# elysium_v0_8.net
KiCad netlist of a schematic drawn in EAGLE
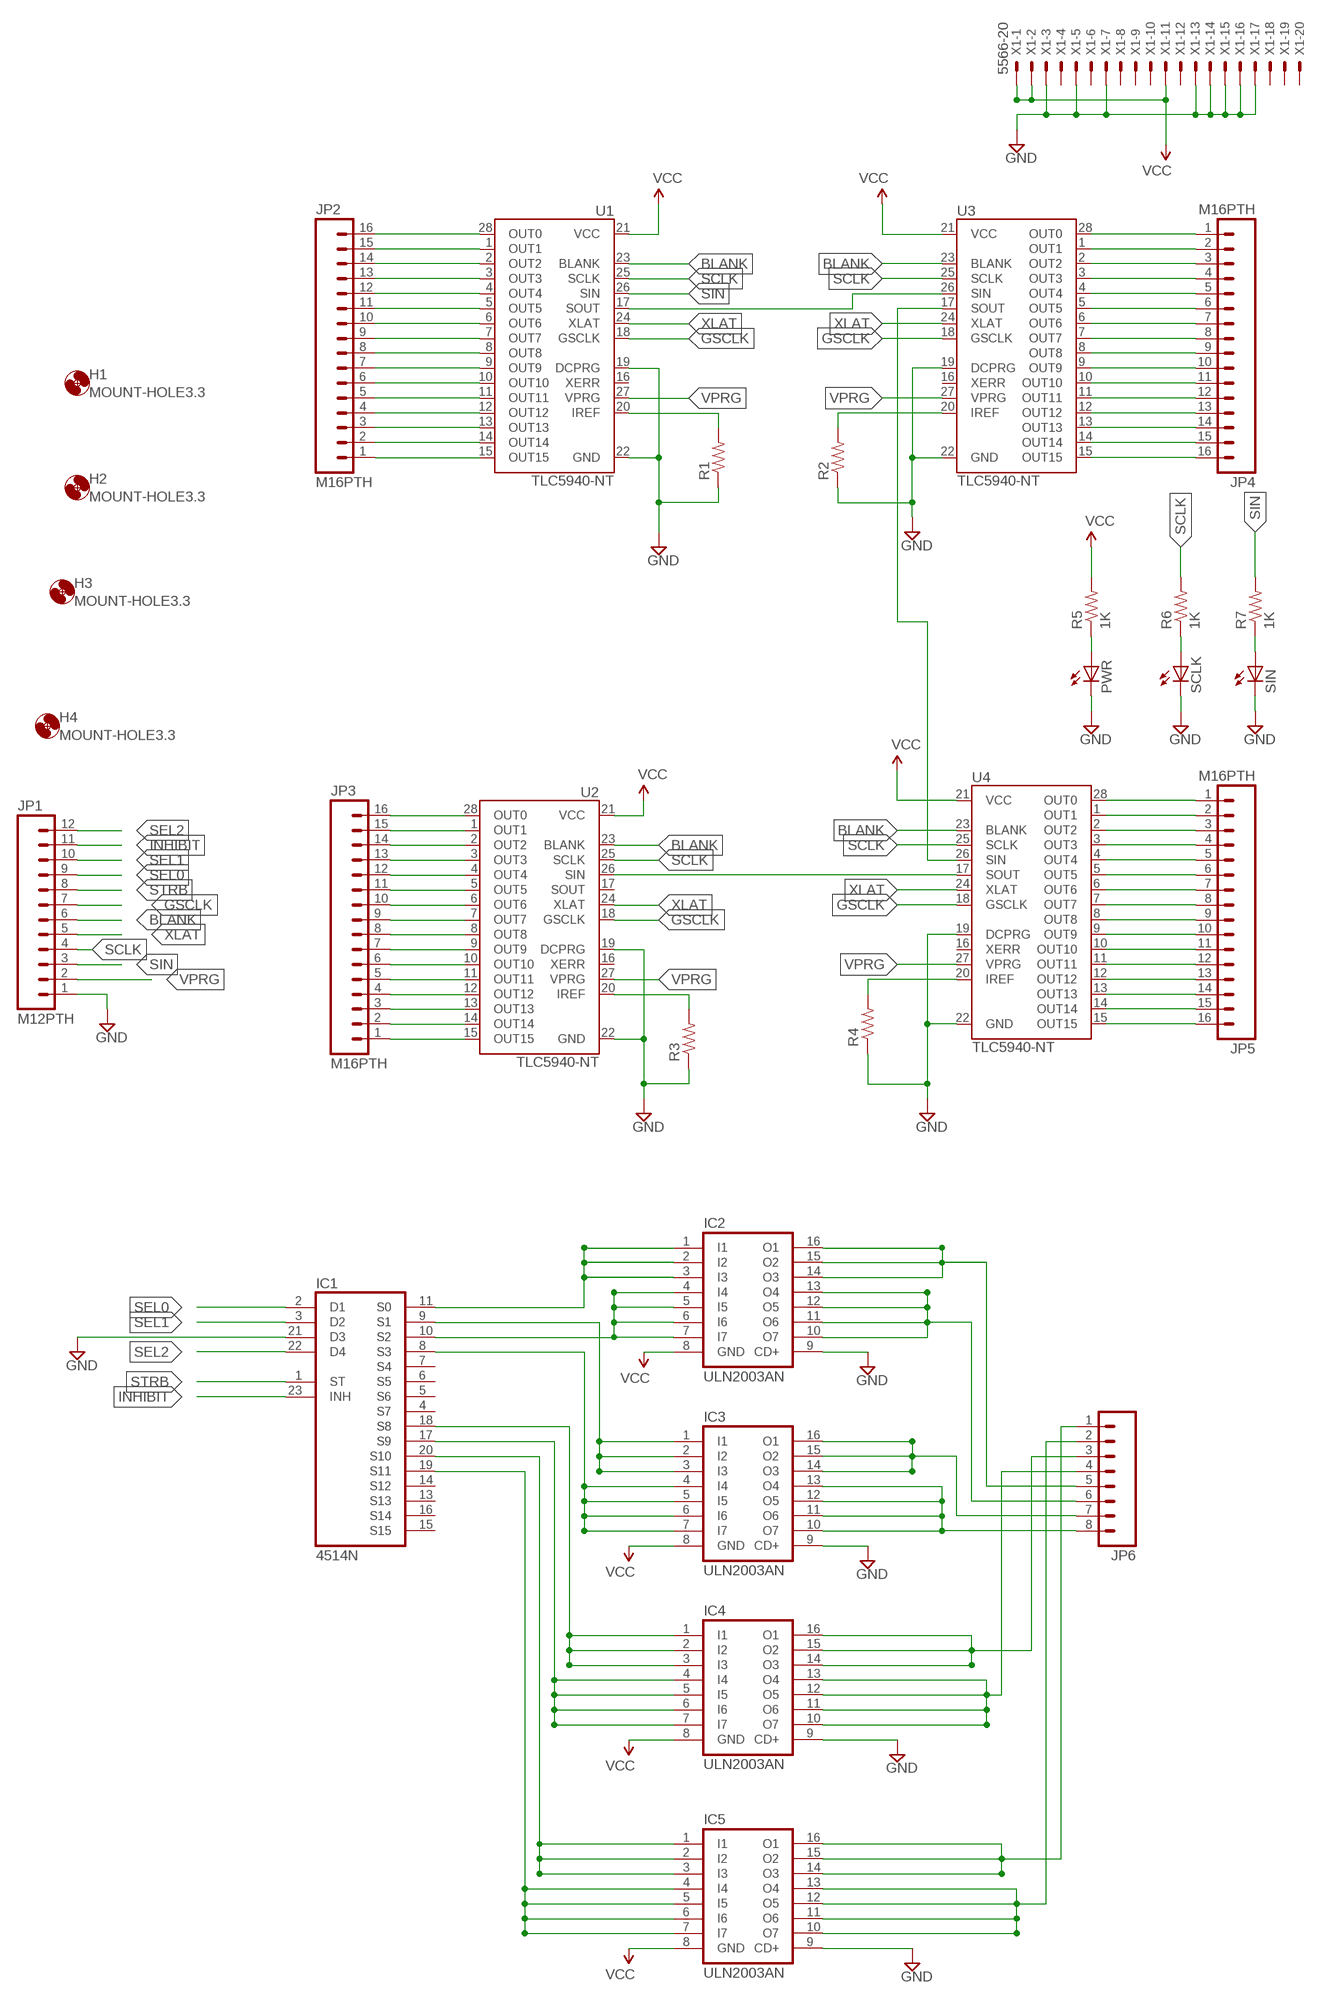
[diagram p0: schematic, sheet 1]

(export (version "E")
  (design (tool "Eeschema 10.0.6"))
  (components
    (comp (ref "H1")
      (value "MOUNT-HOLE3.3")
      (footprint "eagle-import:3,3")
      (libsource (lib "eagle-import") (part "MOUNT-HOLE3.3"))
    )
    (comp (ref "H2")
      (value "MOUNT-HOLE3.3")
      (footprint "eagle-import:3,3")
      (libsource (lib "eagle-import") (part "MOUNT-HOLE3.3"))
    )
    (comp (ref "H3")
      (value "MOUNT-HOLE3.3")
      (footprint "eagle-import:3,3")
      (libsource (lib "eagle-import") (part "MOUNT-HOLE3.3"))
    )
    (comp (ref "H4")
      (value "MOUNT-HOLE3.3")
      (footprint "eagle-import:3,3")
      (libsource (lib "eagle-import") (part "MOUNT-HOLE3.3"))
    )
    (comp (ref "IC1")
      (value "4514N")
      (footprint "eagle-import:DIL24-6")
      (libsource (lib "eagle-import") (part "4514N"))
    )
    (comp (ref "IC2")
      (value "ULN2003AN")
      (footprint "eagle-import:DIL16")
      (libsource (lib "eagle-import") (part "ULN2003AN"))
    )
    (comp (ref "IC3")
      (value "ULN2003AN")
      (footprint "eagle-import:DIL16")
      (libsource (lib "eagle-import") (part "ULN2003AN"))
    )
    (comp (ref "IC4")
      (value "ULN2003AN")
      (footprint "eagle-import:DIL16")
      (libsource (lib "eagle-import") (part "ULN2003AN"))
    )
    (comp (ref "IC5")
      (value "ULN2003AN")
      (footprint "eagle-import:DIL16")
      (libsource (lib "eagle-import") (part "ULN2003AN"))
    )
    (comp (ref "JP1")
      (value "M12PTH")
      (footprint "eagle-import:1X12")
      (libsource (lib "eagle-import") (part "M12PTH"))
    )
    (comp (ref "JP2")
      (value "M16PTH")
      (footprint "eagle-import:1X16")
      (libsource (lib "eagle-import") (part "M16PTH"))
    )
    (comp (ref "JP3")
      (value "M16PTH")
      (footprint "eagle-import:1X16")
      (libsource (lib "eagle-import") (part "M16PTH"))
    )
    (comp (ref "JP4")
      (value "M16PTH")
      (footprint "eagle-import:1X16")
      (libsource (lib "eagle-import") (part "M16PTH"))
    )
    (comp (ref "JP5")
      (value "M16PTH")
      (footprint "eagle-import:1X16")
      (libsource (lib "eagle-import") (part "M16PTH"))
    )
    (comp (ref "JP6")
      (value "M081X08")
      (footprint "eagle-import:1X08")
      (libsource (lib "eagle-import") (part "M081X08"))
    )
    (comp (ref "PWR")
      (value "LED5MM")
      (footprint "eagle-import:LED5MM")
      (libsource (lib "eagle-import") (part "LED5MM"))
    )
    (comp (ref "R1")
      (value "RESISTOREZ")
      (footprint "eagle-import:AXIAL-0.3EZ")
      (libsource (lib "eagle-import") (part "RESISTOREZ"))
    )
    (comp (ref "R2")
      (value "RESISTOREZ")
      (footprint "eagle-import:AXIAL-0.3EZ")
      (libsource (lib "eagle-import") (part "RESISTOREZ"))
    )
    (comp (ref "R3")
      (value "RESISTOREZ")
      (footprint "eagle-import:AXIAL-0.3EZ")
      (libsource (lib "eagle-import") (part "RESISTOREZ"))
    )
    (comp (ref "R4")
      (value "RESISTOREZ")
      (footprint "eagle-import:AXIAL-0.3EZ")
      (libsource (lib "eagle-import") (part "RESISTOREZ"))
    )
    (comp (ref "R5")
      (value "1K")
      (footprint "eagle-import:AXIAL-0.3EZ")
      (libsource (lib "eagle-import") (part "RESISTOREZ"))
    )
    (comp (ref "R6")
      (value "1K")
      (footprint "eagle-import:AXIAL-0.3EZ")
      (libsource (lib "eagle-import") (part "RESISTOREZ"))
    )
    (comp (ref "R7")
      (value "1K")
      (footprint "eagle-import:AXIAL-0.3EZ")
      (libsource (lib "eagle-import") (part "RESISTOREZ"))
    )
    (comp (ref "SCLK")
      (value "LED5MM")
      (footprint "eagle-import:LED5MM")
      (libsource (lib "eagle-import") (part "LED5MM"))
    )
    (comp (ref "SIN")
      (value "LED5MM")
      (footprint "eagle-import:LED5MM")
      (libsource (lib "eagle-import") (part "LED5MM"))
    )
    (comp (ref "U1")
      (value "TLC5940-NT")
      (footprint "eagle-import:DIL28-3")
      (libsource (lib "eagle-import") (part "TLC5940-NT"))
    )
    (comp (ref "U2")
      (value "TLC5940-NT")
      (footprint "eagle-import:DIL28-3")
      (libsource (lib "eagle-import") (part "TLC5940-NT"))
    )
    (comp (ref "U3")
      (value "TLC5940-NT")
      (footprint "eagle-import:DIL28-3")
      (libsource (lib "eagle-import") (part "TLC5940-NT"))
    )
    (comp (ref "U4")
      (value "TLC5940-NT")
      (footprint "eagle-import:DIL28-3")
      (libsource (lib "eagle-import") (part "TLC5940-NT"))
    )
    (comp (ref "X1")
      (value "5566-20")
      (footprint "eagle-import:5566-20")
      (libsource (lib "eagle-import") (part "5566-20"))
    )
  )
  (nets
    (net (code "1") (name "BLANK") (class "Default")
      (node (ref "JP1") (pin "6") (pinfunction "6_6") (pintype "passive"))
      (node (ref "U1") (pin "23") (pinfunction "BLANK_23") (pintype "bidirectional"))
      (node (ref "U2") (pin "23") (pinfunction "BLANK_23") (pintype "bidirectional"))
      (node (ref "U3") (pin "23") (pinfunction "BLANK_23") (pintype "bidirectional"))
      (node (ref "U4") (pin "23") (pinfunction "BLANK_23") (pintype "bidirectional"))
    )
    (net (code "2") (name "GND") (class "Default")
      (node (ref "IC1") (pin "21") (pinfunction "D3_21") (pintype "input"))
      (node (ref "IC2") (pin "9") (pinfunction "CD+_9") (pintype "passive"))
      (node (ref "IC3") (pin "9") (pinfunction "CD+_9") (pintype "passive"))
      (node (ref "IC4") (pin "9") (pinfunction "CD+_9") (pintype "passive"))
      (node (ref "IC5") (pin "9") (pinfunction "CD+_9") (pintype "passive"))
      (node (ref "JP1") (pin "1") (pinfunction "1_1") (pintype "passive"))
      (node (ref "PWR") (pin "K") (pinfunction "C_K") (pintype "passive"))
      (node (ref "R1") (pin "P$1") (pinfunction "1_P$1") (pintype "passive"))
      (node (ref "R2") (pin "P$1") (pinfunction "1_P$1") (pintype "passive"))
      (node (ref "R3") (pin "P$1") (pinfunction "1_P$1") (pintype "passive"))
      (node (ref "R4") (pin "P$1") (pinfunction "1_P$1") (pintype "passive"))
      (node (ref "SCLK") (pin "K") (pinfunction "C_K") (pintype "passive"))
      (node (ref "SIN") (pin "K") (pinfunction "C_K") (pintype "passive"))
      (node (ref "U1") (pin "19") (pinfunction "DCPRG_19") (pintype "bidirectional"))
      (node (ref "U1") (pin "22") (pinfunction "GND_22") (pintype "bidirectional"))
      (node (ref "U2") (pin "19") (pinfunction "DCPRG_19") (pintype "bidirectional"))
      (node (ref "U2") (pin "22") (pinfunction "GND_22") (pintype "bidirectional"))
      (node (ref "U3") (pin "19") (pinfunction "DCPRG_19") (pintype "bidirectional"))
      (node (ref "U3") (pin "22") (pinfunction "GND_22") (pintype "bidirectional"))
      (node (ref "U4") (pin "19") (pinfunction "DCPRG_19") (pintype "bidirectional"))
      (node (ref "U4") (pin "22") (pinfunction "GND_22") (pintype "bidirectional"))
      (node (ref "X1") (pin "13") (pinfunction "S_13") (pintype "passive"))
      (node (ref "X1") (pin "14") (pinfunction "S_14") (pintype "passive"))
      (node (ref "X1") (pin "15") (pinfunction "S_15") (pintype "passive"))
      (node (ref "X1") (pin "16") (pinfunction "S_16") (pintype "passive"))
      (node (ref "X1") (pin "17") (pinfunction "S_17") (pintype "passive"))
      (node (ref "X1") (pin "3") (pinfunction "S_3") (pintype "passive"))
      (node (ref "X1") (pin "5") (pinfunction "S_5") (pintype "passive"))
      (node (ref "X1") (pin "7") (pinfunction "S_7") (pintype "passive"))
    )
    (net (code "3") (name "GSCLK") (class "Default")
      (node (ref "JP1") (pin "7") (pinfunction "7_7") (pintype "passive"))
      (node (ref "U1") (pin "18") (pinfunction "GSCLK_18") (pintype "bidirectional"))
      (node (ref "U2") (pin "18") (pinfunction "GSCLK_18") (pintype "bidirectional"))
      (node (ref "U3") (pin "18") (pinfunction "GSCLK_18") (pintype "bidirectional"))
      (node (ref "U4") (pin "18") (pinfunction "GSCLK_18") (pintype "bidirectional"))
    )
    (net (code "4") (name "INHIBIT") (class "Default")
      (node (ref "IC1") (pin "23") (pinfunction "INH_23") (pintype "input"))
      (node (ref "JP1") (pin "11") (pinfunction "11_11") (pintype "passive"))
    )
    (net (code "5") (name "Net-(IC1A-S0)") (class "Default")
      (node (ref "IC1") (pin "11") (pinfunction "S0_11") (pintype "output"))
      (node (ref "IC2") (pin "1") (pinfunction "I1_1") (pintype "input"))
      (node (ref "IC2") (pin "2") (pinfunction "I2_2") (pintype "input"))
      (node (ref "IC2") (pin "3") (pinfunction "I3_3") (pintype "input"))
    )
    (net (code "6") (name "Net-(IC1A-S1)") (class "Default")
      (node (ref "IC1") (pin "9") (pinfunction "S1_9") (pintype "output"))
      (node (ref "IC3") (pin "1") (pinfunction "I1_1") (pintype "input"))
      (node (ref "IC3") (pin "2") (pinfunction "I2_2") (pintype "input"))
      (node (ref "IC3") (pin "3") (pinfunction "I3_3") (pintype "input"))
    )
    (net (code "7") (name "Net-(IC1A-S2)") (class "Default")
      (node (ref "IC1") (pin "10") (pinfunction "S2_10") (pintype "output"))
      (node (ref "IC2") (pin "4") (pinfunction "I4_4") (pintype "input"))
      (node (ref "IC2") (pin "5") (pinfunction "I5_5") (pintype "input"))
      (node (ref "IC2") (pin "6") (pinfunction "I6_6") (pintype "input"))
      (node (ref "IC2") (pin "7") (pinfunction "I7_7") (pintype "input"))
    )
    (net (code "8") (name "Net-(IC1A-S3)") (class "Default")
      (node (ref "IC1") (pin "8") (pinfunction "S3_8") (pintype "output"))
      (node (ref "IC3") (pin "4") (pinfunction "I4_4") (pintype "input"))
      (node (ref "IC3") (pin "5") (pinfunction "I5_5") (pintype "input"))
      (node (ref "IC3") (pin "6") (pinfunction "I6_6") (pintype "input"))
      (node (ref "IC3") (pin "7") (pinfunction "I7_7") (pintype "input"))
    )
    (net (code "9") (name "Net-(IC1A-S8)") (class "Default")
      (node (ref "IC1") (pin "18") (pinfunction "S8_18") (pintype "output"))
      (node (ref "IC4") (pin "1") (pinfunction "I1_1") (pintype "input"))
      (node (ref "IC4") (pin "2") (pinfunction "I2_2") (pintype "input"))
      (node (ref "IC4") (pin "3") (pinfunction "I3_3") (pintype "input"))
    )
    (net (code "10") (name "Net-(IC1A-S9)") (class "Default")
      (node (ref "IC1") (pin "17") (pinfunction "S9_17") (pintype "output"))
      (node (ref "IC4") (pin "4") (pinfunction "I4_4") (pintype "input"))
      (node (ref "IC4") (pin "5") (pinfunction "I5_5") (pintype "input"))
      (node (ref "IC4") (pin "6") (pinfunction "I6_6") (pintype "input"))
      (node (ref "IC4") (pin "7") (pinfunction "I7_7") (pintype "input"))
    )
    (net (code "11") (name "Net-(IC1A-S10)") (class "Default")
      (node (ref "IC1") (pin "20") (pinfunction "S10_20") (pintype "output"))
      (node (ref "IC5") (pin "1") (pinfunction "I1_1") (pintype "input"))
      (node (ref "IC5") (pin "2") (pinfunction "I2_2") (pintype "input"))
      (node (ref "IC5") (pin "3") (pinfunction "I3_3") (pintype "input"))
    )
    (net (code "12") (name "Net-(IC1A-S11)") (class "Default")
      (node (ref "IC1") (pin "19") (pinfunction "S11_19") (pintype "output"))
      (node (ref "IC5") (pin "4") (pinfunction "I4_4") (pintype "input"))
      (node (ref "IC5") (pin "5") (pinfunction "I5_5") (pintype "input"))
      (node (ref "IC5") (pin "6") (pinfunction "I6_6") (pintype "input"))
      (node (ref "IC5") (pin "7") (pinfunction "I7_7") (pintype "input"))
    )
    (net (code "13") (name "Net-(IC2-O1)") (class "Default")
      (node (ref "IC2") (pin "14") (pinfunction "O3_14") (pintype "open_collector"))
      (node (ref "IC2") (pin "15") (pinfunction "O2_15") (pintype "open_collector"))
      (node (ref "IC2") (pin "16") (pinfunction "O1_16") (pintype "open_collector"))
      (node (ref "JP6") (pin "5") (pinfunction "5_5") (pintype "passive"))
    )
    (net (code "14") (name "Net-(IC2-O4)") (class "Default")
      (node (ref "IC2") (pin "10") (pinfunction "O7_10") (pintype "open_collector"))
      (node (ref "IC2") (pin "11") (pinfunction "O6_11") (pintype "open_collector"))
      (node (ref "IC2") (pin "12") (pinfunction "O5_12") (pintype "open_collector"))
      (node (ref "IC2") (pin "13") (pinfunction "O4_13") (pintype "open_collector"))
      (node (ref "JP6") (pin "6") (pinfunction "6_6") (pintype "passive"))
    )
    (net (code "15") (name "Net-(IC3-O1)") (class "Default")
      (node (ref "IC3") (pin "14") (pinfunction "O3_14") (pintype "open_collector"))
      (node (ref "IC3") (pin "15") (pinfunction "O2_15") (pintype "open_collector"))
      (node (ref "IC3") (pin "16") (pinfunction "O1_16") (pintype "open_collector"))
      (node (ref "JP6") (pin "7") (pinfunction "7_7") (pintype "passive"))
    )
    (net (code "16") (name "Net-(IC3-O4)") (class "Default")
      (node (ref "IC3") (pin "10") (pinfunction "O7_10") (pintype "open_collector"))
      (node (ref "IC3") (pin "11") (pinfunction "O6_11") (pintype "open_collector"))
      (node (ref "IC3") (pin "12") (pinfunction "O5_12") (pintype "open_collector"))
      (node (ref "IC3") (pin "13") (pinfunction "O4_13") (pintype "open_collector"))
      (node (ref "JP6") (pin "8") (pinfunction "8_8") (pintype "passive"))
    )
    (net (code "17") (name "Net-(IC4-O1)") (class "Default")
      (node (ref "IC4") (pin "14") (pinfunction "O3_14") (pintype "open_collector"))
      (node (ref "IC4") (pin "15") (pinfunction "O2_15") (pintype "open_collector"))
      (node (ref "IC4") (pin "16") (pinfunction "O1_16") (pintype "open_collector"))
      (node (ref "JP6") (pin "3") (pinfunction "3_3") (pintype "passive"))
    )
    (net (code "18") (name "Net-(IC4-O4)") (class "Default")
      (node (ref "IC4") (pin "10") (pinfunction "O7_10") (pintype "open_collector"))
      (node (ref "IC4") (pin "11") (pinfunction "O6_11") (pintype "open_collector"))
      (node (ref "IC4") (pin "12") (pinfunction "O5_12") (pintype "open_collector"))
      (node (ref "IC4") (pin "13") (pinfunction "O4_13") (pintype "open_collector"))
      (node (ref "JP6") (pin "4") (pinfunction "4_4") (pintype "passive"))
    )
    (net (code "19") (name "Net-(IC5-O1)") (class "Default")
      (node (ref "IC5") (pin "14") (pinfunction "O3_14") (pintype "open_collector"))
      (node (ref "IC5") (pin "15") (pinfunction "O2_15") (pintype "open_collector"))
      (node (ref "IC5") (pin "16") (pinfunction "O1_16") (pintype "open_collector"))
      (node (ref "JP6") (pin "1") (pinfunction "1_1") (pintype "passive"))
    )
    (net (code "20") (name "Net-(IC5-O4)") (class "Default")
      (node (ref "IC5") (pin "10") (pinfunction "O7_10") (pintype "open_collector"))
      (node (ref "IC5") (pin "11") (pinfunction "O6_11") (pintype "open_collector"))
      (node (ref "IC5") (pin "12") (pinfunction "O5_12") (pintype "open_collector"))
      (node (ref "IC5") (pin "13") (pinfunction "O4_13") (pintype "open_collector"))
      (node (ref "JP6") (pin "2") (pinfunction "2_2") (pintype "passive"))
    )
    (net (code "21") (name "Net-(R1-2)") (class "Default")
      (node (ref "R1") (pin "P$2") (pinfunction "2_P$2") (pintype "passive"))
      (node (ref "U1") (pin "20") (pinfunction "IREF_20") (pintype "bidirectional"))
    )
    (net (code "22") (name "Net-(R2-2)") (class "Default")
      (node (ref "R2") (pin "P$2") (pinfunction "2_P$2") (pintype "passive"))
      (node (ref "U3") (pin "20") (pinfunction "IREF_20") (pintype "bidirectional"))
    )
    (net (code "23") (name "Net-(R3-2)") (class "Default")
      (node (ref "R3") (pin "P$2") (pinfunction "2_P$2") (pintype "passive"))
      (node (ref "U2") (pin "20") (pinfunction "IREF_20") (pintype "bidirectional"))
    )
    (net (code "24") (name "Net-(R4-2)") (class "Default")
      (node (ref "R4") (pin "P$2") (pinfunction "2_P$2") (pintype "passive"))
      (node (ref "U4") (pin "20") (pinfunction "IREF_20") (pintype "bidirectional"))
    )
    (net (code "25") (name "Net-(R5-1)") (class "Default")
      (node (ref "PWR") (pin "A") (pinfunction "A_A") (pintype "passive"))
      (node (ref "R5") (pin "P$1") (pinfunction "1_P$1") (pintype "passive"))
    )
    (net (code "26") (name "Net-(R6-1)") (class "Default")
      (node (ref "R6") (pin "P$1") (pinfunction "1_P$1") (pintype "passive"))
      (node (ref "SCLK") (pin "A") (pinfunction "A_A") (pintype "passive"))
    )
    (net (code "27") (name "Net-(R7-1)") (class "Default")
      (node (ref "R7") (pin "P$1") (pinfunction "1_P$1") (pintype "passive"))
      (node (ref "SIN") (pin "A") (pinfunction "A_A") (pintype "passive"))
    )
    (net (code "28") (name "Net-(U1-OUT0)") (class "Default")
      (node (ref "JP2") (pin "16") (pinfunction "16_16") (pintype "passive"))
      (node (ref "U1") (pin "28") (pinfunction "OUT0_28") (pintype "bidirectional"))
    )
    (net (code "29") (name "Net-(U1-OUT1)") (class "Default")
      (node (ref "JP2") (pin "15") (pinfunction "15_15") (pintype "passive"))
      (node (ref "U1") (pin "1") (pinfunction "OUT1_1") (pintype "bidirectional"))
    )
    (net (code "30") (name "Net-(U1-OUT2)") (class "Default")
      (node (ref "JP2") (pin "14") (pinfunction "14_14") (pintype "passive"))
      (node (ref "U1") (pin "2") (pinfunction "OUT2_2") (pintype "bidirectional"))
    )
    (net (code "31") (name "Net-(U1-OUT3)") (class "Default")
      (node (ref "JP2") (pin "13") (pinfunction "13_13") (pintype "passive"))
      (node (ref "U1") (pin "3") (pinfunction "OUT3_3") (pintype "bidirectional"))
    )
    (net (code "32") (name "Net-(U1-OUT4)") (class "Default")
      (node (ref "JP2") (pin "12") (pinfunction "12_12") (pintype "passive"))
      (node (ref "U1") (pin "4") (pinfunction "OUT4_4") (pintype "bidirectional"))
    )
    (net (code "33") (name "Net-(U1-OUT5)") (class "Default")
      (node (ref "JP2") (pin "11") (pinfunction "11_11") (pintype "passive"))
      (node (ref "U1") (pin "5") (pinfunction "OUT5_5") (pintype "bidirectional"))
    )
    (net (code "34") (name "Net-(U1-OUT6)") (class "Default")
      (node (ref "JP2") (pin "10") (pinfunction "10_10") (pintype "passive"))
      (node (ref "U1") (pin "6") (pinfunction "OUT6_6") (pintype "bidirectional"))
    )
    (net (code "35") (name "Net-(U1-OUT7)") (class "Default")
      (node (ref "JP2") (pin "9") (pinfunction "9_9") (pintype "passive"))
      (node (ref "U1") (pin "7") (pinfunction "OUT7_7") (pintype "bidirectional"))
    )
    (net (code "36") (name "Net-(U1-OUT8)") (class "Default")
      (node (ref "JP2") (pin "8") (pinfunction "8_8") (pintype "passive"))
      (node (ref "U1") (pin "8") (pinfunction "OUT8_8") (pintype "bidirectional"))
    )
    (net (code "37") (name "Net-(U1-OUT9)") (class "Default")
      (node (ref "JP2") (pin "7") (pinfunction "7_7") (pintype "passive"))
      (node (ref "U1") (pin "9") (pinfunction "OUT9_9") (pintype "bidirectional"))
    )
    (net (code "38") (name "Net-(U1-OUT10)") (class "Default")
      (node (ref "JP2") (pin "6") (pinfunction "6_6") (pintype "passive"))
      (node (ref "U1") (pin "10") (pinfunction "OUT10_10") (pintype "bidirectional"))
    )
    (net (code "39") (name "Net-(U1-OUT11)") (class "Default")
      (node (ref "JP2") (pin "5") (pinfunction "5_5") (pintype "passive"))
      (node (ref "U1") (pin "11") (pinfunction "OUT11_11") (pintype "bidirectional"))
    )
    (net (code "40") (name "Net-(U1-OUT12)") (class "Default")
      (node (ref "JP2") (pin "4") (pinfunction "4_4") (pintype "passive"))
      (node (ref "U1") (pin "12") (pinfunction "OUT12_12") (pintype "bidirectional"))
    )
    (net (code "41") (name "Net-(U1-OUT13)") (class "Default")
      (node (ref "JP2") (pin "3") (pinfunction "3_3") (pintype "passive"))
      (node (ref "U1") (pin "13") (pinfunction "OUT13_13") (pintype "bidirectional"))
    )
    (net (code "42") (name "Net-(U1-OUT14)") (class "Default")
      (node (ref "JP2") (pin "2") (pinfunction "2_2") (pintype "passive"))
      (node (ref "U1") (pin "14") (pinfunction "OUT14_14") (pintype "bidirectional"))
    )
    (net (code "43") (name "Net-(U1-OUT15)") (class "Default")
      (node (ref "JP2") (pin "1") (pinfunction "1_1") (pintype "passive"))
      (node (ref "U1") (pin "15") (pinfunction "OUT15_15") (pintype "bidirectional"))
    )
    (net (code "44") (name "Net-(U1-SOUT)") (class "Default")
      (node (ref "U1") (pin "17") (pinfunction "SOUT_17") (pintype "bidirectional"))
      (node (ref "U3") (pin "26") (pinfunction "SIN_26") (pintype "bidirectional"))
    )
    (net (code "45") (name "Net-(U2-OUT0)") (class "Default")
      (node (ref "JP3") (pin "16") (pinfunction "16_16") (pintype "passive"))
      (node (ref "U2") (pin "28") (pinfunction "OUT0_28") (pintype "bidirectional"))
    )
    (net (code "46") (name "Net-(U2-OUT1)") (class "Default")
      (node (ref "JP3") (pin "15") (pinfunction "15_15") (pintype "passive"))
      (node (ref "U2") (pin "1") (pinfunction "OUT1_1") (pintype "bidirectional"))
    )
    (net (code "47") (name "Net-(U2-OUT2)") (class "Default")
      (node (ref "JP3") (pin "14") (pinfunction "14_14") (pintype "passive"))
      (node (ref "U2") (pin "2") (pinfunction "OUT2_2") (pintype "bidirectional"))
    )
    (net (code "48") (name "Net-(U2-OUT3)") (class "Default")
      (node (ref "JP3") (pin "13") (pinfunction "13_13") (pintype "passive"))
      (node (ref "U2") (pin "3") (pinfunction "OUT3_3") (pintype "bidirectional"))
    )
    (net (code "49") (name "Net-(U2-OUT4)") (class "Default")
      (node (ref "JP3") (pin "12") (pinfunction "12_12") (pintype "passive"))
      (node (ref "U2") (pin "4") (pinfunction "OUT4_4") (pintype "bidirectional"))
    )
    (net (code "50") (name "Net-(U2-OUT5)") (class "Default")
      (node (ref "JP3") (pin "11") (pinfunction "11_11") (pintype "passive"))
      (node (ref "U2") (pin "5") (pinfunction "OUT5_5") (pintype "bidirectional"))
    )
    (net (code "51") (name "Net-(U2-OUT6)") (class "Default")
      (node (ref "JP3") (pin "10") (pinfunction "10_10") (pintype "passive"))
      (node (ref "U2") (pin "6") (pinfunction "OUT6_6") (pintype "bidirectional"))
    )
    (net (code "52") (name "Net-(U2-OUT7)") (class "Default")
      (node (ref "JP3") (pin "9") (pinfunction "9_9") (pintype "passive"))
      (node (ref "U2") (pin "7") (pinfunction "OUT7_7") (pintype "bidirectional"))
    )
    (net (code "53") (name "Net-(U2-OUT8)") (class "Default")
      (node (ref "JP3") (pin "8") (pinfunction "8_8") (pintype "passive"))
      (node (ref "U2") (pin "8") (pinfunction "OUT8_8") (pintype "bidirectional"))
    )
    (net (code "54") (name "Net-(U2-OUT9)") (class "Default")
      (node (ref "JP3") (pin "7") (pinfunction "7_7") (pintype "passive"))
      (node (ref "U2") (pin "9") (pinfunction "OUT9_9") (pintype "bidirectional"))
    )
    (net (code "55") (name "Net-(U2-OUT10)") (class "Default")
      (node (ref "JP3") (pin "6") (pinfunction "6_6") (pintype "passive"))
      (node (ref "U2") (pin "10") (pinfunction "OUT10_10") (pintype "bidirectional"))
    )
    (net (code "56") (name "Net-(U2-OUT11)") (class "Default")
      (node (ref "JP3") (pin "5") (pinfunction "5_5") (pintype "passive"))
      (node (ref "U2") (pin "11") (pinfunction "OUT11_11") (pintype "bidirectional"))
    )
    (net (code "57") (name "Net-(U2-OUT12)") (class "Default")
      (node (ref "JP3") (pin "4") (pinfunction "4_4") (pintype "passive"))
      (node (ref "U2") (pin "12") (pinfunction "OUT12_12") (pintype "bidirectional"))
    )
    (net (code "58") (name "Net-(U2-OUT13)") (class "Default")
      (node (ref "JP3") (pin "3") (pinfunction "3_3") (pintype "passive"))
      (node (ref "U2") (pin "13") (pinfunction "OUT13_13") (pintype "bidirectional"))
    )
    (net (code "59") (name "Net-(U2-OUT14)") (class "Default")
      (node (ref "JP3") (pin "2") (pinfunction "2_2") (pintype "passive"))
      (node (ref "U2") (pin "14") (pinfunction "OUT14_14") (pintype "bidirectional"))
    )
    (net (code "60") (name "Net-(U2-OUT15)") (class "Default")
      (node (ref "JP3") (pin "1") (pinfunction "1_1") (pintype "passive"))
      (node (ref "U2") (pin "15") (pinfunction "OUT15_15") (pintype "bidirectional"))
    )
    (net (code "61") (name "Net-(U2-SIN)") (class "Default")
      (node (ref "U2") (pin "26") (pinfunction "SIN_26") (pintype "bidirectional"))
      (node (ref "U4") (pin "17") (pinfunction "SOUT_17") (pintype "bidirectional"))
    )
    (net (code "62") (name "Net-(U3-OUT0)") (class "Default")
      (node (ref "JP4") (pin "1") (pinfunction "1_1") (pintype "passive"))
      (node (ref "U3") (pin "28") (pinfunction "OUT0_28") (pintype "bidirectional"))
    )
    (net (code "63") (name "Net-(U3-OUT1)") (class "Default")
      (node (ref "JP4") (pin "2") (pinfunction "2_2") (pintype "passive"))
      (node (ref "U3") (pin "1") (pinfunction "OUT1_1") (pintype "bidirectional"))
    )
    (net (code "64") (name "Net-(U3-OUT2)") (class "Default")
      (node (ref "JP4") (pin "3") (pinfunction "3_3") (pintype "passive"))
      (node (ref "U3") (pin "2") (pinfunction "OUT2_2") (pintype "bidirectional"))
    )
    (net (code "65") (name "Net-(U3-OUT3)") (class "Default")
      (node (ref "JP4") (pin "4") (pinfunction "4_4") (pintype "passive"))
      (node (ref "U3") (pin "3") (pinfunction "OUT3_3") (pintype "bidirectional"))
    )
    (net (code "66") (name "Net-(U3-OUT4)") (class "Default")
      (node (ref "JP4") (pin "5") (pinfunction "5_5") (pintype "passive"))
      (node (ref "U3") (pin "4") (pinfunction "OUT4_4") (pintype "bidirectional"))
    )
    (net (code "67") (name "Net-(U3-OUT5)") (class "Default")
      (node (ref "JP4") (pin "6") (pinfunction "6_6") (pintype "passive"))
      (node (ref "U3") (pin "5") (pinfunction "OUT5_5") (pintype "bidirectional"))
    )
    (net (code "68") (name "Net-(U3-OUT6)") (class "Default")
      (node (ref "JP4") (pin "7") (pinfunction "7_7") (pintype "passive"))
      (node (ref "U3") (pin "6") (pinfunction "OUT6_6") (pintype "bidirectional"))
    )
    (net (code "69") (name "Net-(U3-OUT7)") (class "Default")
      (node (ref "JP4") (pin "8") (pinfunction "8_8") (pintype "passive"))
      (node (ref "U3") (pin "7") (pinfunction "OUT7_7") (pintype "bidirectional"))
    )
    (net (code "70") (name "Net-(U3-OUT8)") (class "Default")
      (node (ref "JP4") (pin "9") (pinfunction "9_9") (pintype "passive"))
      (node (ref "U3") (pin "8") (pinfunction "OUT8_8") (pintype "bidirectional"))
    )
    (net (code "71") (name "Net-(U3-OUT9)") (class "Default")
      (node (ref "JP4") (pin "10") (pinfunction "10_10") (pintype "passive"))
      (node (ref "U3") (pin "9") (pinfunction "OUT9_9") (pintype "bidirectional"))
    )
    (net (code "72") (name "Net-(U3-OUT10)") (class "Default")
      (node (ref "JP4") (pin "11") (pinfunction "11_11") (pintype "passive"))
      (node (ref "U3") (pin "10") (pinfunction "OUT10_10") (pintype "bidirectional"))
    )
    (net (code "73") (name "Net-(U3-OUT11)") (class "Default")
      (node (ref "JP4") (pin "12") (pinfunction "12_12") (pintype "passive"))
      (node (ref "U3") (pin "11") (pinfunction "OUT11_11") (pintype "bidirectional"))
    )
    (net (code "74") (name "Net-(U3-OUT12)") (class "Default")
      (node (ref "JP4") (pin "13") (pinfunction "13_13") (pintype "passive"))
      (node (ref "U3") (pin "12") (pinfunction "OUT12_12") (pintype "bidirectional"))
    )
    (net (code "75") (name "Net-(U3-OUT13)") (class "Default")
      (node (ref "JP4") (pin "14") (pinfunction "14_14") (pintype "passive"))
      (node (ref "U3") (pin "13") (pinfunction "OUT13_13") (pintype "bidirectional"))
    )
    (net (code "76") (name "Net-(U3-OUT14)") (class "Default")
      (node (ref "JP4") (pin "15") (pinfunction "15_15") (pintype "passive"))
      (node (ref "U3") (pin "14") (pinfunction "OUT14_14") (pintype "bidirectional"))
    )
    (net (code "77") (name "Net-(U3-OUT15)") (class "Default")
      (node (ref "JP4") (pin "16") (pinfunction "16_16") (pintype "passive"))
      (node (ref "U3") (pin "15") (pinfunction "OUT15_15") (pintype "bidirectional"))
    )
    (net (code "78") (name "Net-(U3-SOUT)") (class "Default")
      (node (ref "U3") (pin "17") (pinfunction "SOUT_17") (pintype "bidirectional"))
      (node (ref "U4") (pin "26") (pinfunction "SIN_26") (pintype "bidirectional"))
    )
    (net (code "79") (name "Net-(U4-OUT0)") (class "Default")
      (node (ref "JP5") (pin "1") (pinfunction "1_1") (pintype "passive"))
      (node (ref "U4") (pin "28") (pinfunction "OUT0_28") (pintype "bidirectional"))
    )
    (net (code "80") (name "Net-(U4-OUT1)") (class "Default")
      (node (ref "JP5") (pin "2") (pinfunction "2_2") (pintype "passive"))
      (node (ref "U4") (pin "1") (pinfunction "OUT1_1") (pintype "bidirectional"))
    )
    (net (code "81") (name "Net-(U4-OUT2)") (class "Default")
      (node (ref "JP5") (pin "3") (pinfunction "3_3") (pintype "passive"))
      (node (ref "U4") (pin "2") (pinfunction "OUT2_2") (pintype "bidirectional"))
    )
    (net (code "82") (name "Net-(U4-OUT3)") (class "Default")
      (node (ref "JP5") (pin "4") (pinfunction "4_4") (pintype "passive"))
      (node (ref "U4") (pin "3") (pinfunction "OUT3_3") (pintype "bidirectional"))
    )
    (net (code "83") (name "Net-(U4-OUT4)") (class "Default")
      (node (ref "JP5") (pin "5") (pinfunction "5_5") (pintype "passive"))
      (node (ref "U4") (pin "4") (pinfunction "OUT4_4") (pintype "bidirectional"))
    )
    (net (code "84") (name "Net-(U4-OUT5)") (class "Default")
      (node (ref "JP5") (pin "6") (pinfunction "6_6") (pintype "passive"))
      (node (ref "U4") (pin "5") (pinfunction "OUT5_5") (pintype "bidirectional"))
    )
    (net (code "85") (name "Net-(U4-OUT6)") (class "Default")
      (node (ref "JP5") (pin "7") (pinfunction "7_7") (pintype "passive"))
      (node (ref "U4") (pin "6") (pinfunction "OUT6_6") (pintype "bidirectional"))
    )
    (net (code "86") (name "Net-(U4-OUT7)") (class "Default")
      (node (ref "JP5") (pin "8") (pinfunction "8_8") (pintype "passive"))
      (node (ref "U4") (pin "7") (pinfunction "OUT7_7") (pintype "bidirectional"))
    )
    (net (code "87") (name "Net-(U4-OUT8)") (class "Default")
      (node (ref "JP5") (pin "9") (pinfunction "9_9") (pintype "passive"))
      (node (ref "U4") (pin "8") (pinfunction "OUT8_8") (pintype "bidirectional"))
    )
    (net (code "88") (name "Net-(U4-OUT9)") (class "Default")
      (node (ref "JP5") (pin "10") (pinfunction "10_10") (pintype "passive"))
      (node (ref "U4") (pin "9") (pinfunction "OUT9_9") (pintype "bidirectional"))
    )
    (net (code "89") (name "Net-(U4-OUT10)") (class "Default")
      (node (ref "JP5") (pin "11") (pinfunction "11_11") (pintype "passive"))
      (node (ref "U4") (pin "10") (pinfunction "OUT10_10") (pintype "bidirectional"))
    )
    (net (code "90") (name "Net-(U4-OUT11)") (class "Default")
      (node (ref "JP5") (pin "12") (pinfunction "12_12") (pintype "passive"))
      (node (ref "U4") (pin "11") (pinfunction "OUT11_11") (pintype "bidirectional"))
    )
    (net (code "91") (name "Net-(U4-OUT12)") (class "Default")
      (node (ref "JP5") (pin "13") (pinfunction "13_13") (pintype "passive"))
      (node (ref "U4") (pin "12") (pinfunction "OUT12_12") (pintype "bidirectional"))
    )
    (net (code "92") (name "Net-(U4-OUT13)") (class "Default")
      (node (ref "JP5") (pin "14") (pinfunction "14_14") (pintype "passive"))
      (node (ref "U4") (pin "13") (pinfunction "OUT13_13") (pintype "bidirectional"))
    )
    (net (code "93") (name "Net-(U4-OUT14)") (class "Default")
      (node (ref "JP5") (pin "15") (pinfunction "15_15") (pintype "passive"))
      (node (ref "U4") (pin "14") (pinfunction "OUT14_14") (pintype "bidirectional"))
    )
    (net (code "94") (name "Net-(U4-OUT15)") (class "Default")
      (node (ref "JP5") (pin "16") (pinfunction "16_16") (pintype "passive"))
      (node (ref "U4") (pin "15") (pinfunction "OUT15_15") (pintype "bidirectional"))
    )
    (net (code "95") (name "SCLK") (class "Default")
      (node (ref "JP1") (pin "4") (pinfunction "4_4") (pintype "passive"))
      (node (ref "R6") (pin "P$2") (pinfunction "2_P$2") (pintype "passive"))
      (node (ref "U1") (pin "25") (pinfunction "SCLK_25") (pintype "bidirectional"))
      (node (ref "U2") (pin "25") (pinfunction "SCLK_25") (pintype "bidirectional"))
      (node (ref "U3") (pin "25") (pinfunction "SCLK_25") (pintype "bidirectional"))
      (node (ref "U4") (pin "25") (pinfunction "SCLK_25") (pintype "bidirectional"))
    )
    (net (code "96") (name "SEL0") (class "Default")
      (node (ref "IC1") (pin "2") (pinfunction "D1_2") (pintype "input"))
      (node (ref "JP1") (pin "9") (pinfunction "9_9") (pintype "passive"))
    )
    (net (code "97") (name "SEL1") (class "Default")
      (node (ref "IC1") (pin "3") (pinfunction "D2_3") (pintype "input"))
      (node (ref "JP1") (pin "10") (pinfunction "10_10") (pintype "passive"))
    )
    (net (code "98") (name "SEL2") (class "Default")
      (node (ref "IC1") (pin "22") (pinfunction "D4_22") (pintype "input"))
      (node (ref "JP1") (pin "12") (pinfunction "12_12") (pintype "passive"))
    )
    (net (code "99") (name "SIN") (class "Default")
      (node (ref "JP1") (pin "3") (pinfunction "3_3") (pintype "passive"))
      (node (ref "R7") (pin "P$2") (pinfunction "2_P$2") (pintype "passive"))
      (node (ref "U1") (pin "26") (pinfunction "SIN_26") (pintype "bidirectional"))
    )
    (net (code "100") (name "STRB") (class "Default")
      (node (ref "IC1") (pin "1") (pinfunction "ST_1") (pintype "input"))
      (node (ref "JP1") (pin "8") (pinfunction "8_8") (pintype "passive"))
    )
    (net (code "101") (name "VCC") (class "Default")
      (node (ref "IC2") (pin "8") (pinfunction "GND_8") (pintype "power_in"))
      (node (ref "IC3") (pin "8") (pinfunction "GND_8") (pintype "power_in"))
      (node (ref "IC4") (pin "8") (pinfunction "GND_8") (pintype "power_in"))
      (node (ref "IC5") (pin "8") (pinfunction "GND_8") (pintype "power_in"))
      (node (ref "R5") (pin "P$2") (pinfunction "2_P$2") (pintype "passive"))
      (node (ref "U1") (pin "21") (pinfunction "VCC_21") (pintype "bidirectional"))
      (node (ref "U2") (pin "21") (pinfunction "VCC_21") (pintype "bidirectional"))
      (node (ref "U3") (pin "21") (pinfunction "VCC_21") (pintype "bidirectional"))
      (node (ref "U4") (pin "21") (pinfunction "VCC_21") (pintype "bidirectional"))
      (node (ref "X1") (pin "1") (pinfunction "S_1") (pintype "passive"))
      (node (ref "X1") (pin "11") (pinfunction "S_11") (pintype "passive"))
      (node (ref "X1") (pin "2") (pinfunction "S_2") (pintype "passive"))
    )
    (net (code "102") (name "VPRG") (class "Default")
      (node (ref "JP1") (pin "2") (pinfunction "2_2") (pintype "passive"))
      (node (ref "U1") (pin "27") (pinfunction "VPRG_27") (pintype "bidirectional"))
      (node (ref "U2") (pin "27") (pinfunction "VPRG_27") (pintype "bidirectional"))
      (node (ref "U3") (pin "27") (pinfunction "VPRG_27") (pintype "bidirectional"))
      (node (ref "U4") (pin "27") (pinfunction "VPRG_27") (pintype "bidirectional"))
    )
    (net (code "103") (name "XLAT") (class "Default")
      (node (ref "JP1") (pin "5") (pinfunction "5_5") (pintype "passive"))
      (node (ref "U1") (pin "24") (pinfunction "XLAT_24") (pintype "bidirectional"))
      (node (ref "U2") (pin "24") (pinfunction "XLAT_24") (pintype "bidirectional"))
      (node (ref "U3") (pin "24") (pinfunction "XLAT_24") (pintype "bidirectional"))
      (node (ref "U4") (pin "24") (pinfunction "XLAT_24") (pintype "bidirectional"))
    )
    (net (code "104") (name "unconnected-(IC1A-S4-Pad7)") (class "Default")
      (node (ref "IC1") (pin "7") (pinfunction "S4_7") (pintype "output"))
    )
    (net (code "105") (name "unconnected-(IC1A-S5-Pad6)") (class "Default")
      (node (ref "IC1") (pin "6") (pinfunction "S5_6") (pintype "output"))
    )
    (net (code "106") (name "unconnected-(IC1A-S6-Pad5)") (class "Default")
      (node (ref "IC1") (pin "5") (pinfunction "S6_5") (pintype "output"))
    )
    (net (code "107") (name "unconnected-(IC1A-S7-Pad4)") (class "Default")
      (node (ref "IC1") (pin "4") (pinfunction "S7_4") (pintype "output"))
    )
    (net (code "108") (name "unconnected-(IC1A-S12-Pad14)") (class "Default")
      (node (ref "IC1") (pin "14") (pinfunction "S12_14") (pintype "output"))
    )
    (net (code "109") (name "unconnected-(IC1A-S13-Pad13)") (class "Default")
      (node (ref "IC1") (pin "13") (pinfunction "S13_13") (pintype "output"))
    )
    (net (code "110") (name "unconnected-(IC1A-S14-Pad16)") (class "Default")
      (node (ref "IC1") (pin "16") (pinfunction "S14_16") (pintype "output"))
    )
    (net (code "111") (name "unconnected-(IC1A-S15-Pad15)") (class "Default")
      (node (ref "IC1") (pin "15") (pinfunction "S15_15") (pintype "output"))
    )
    (net (code "112") (name "unconnected-(U1-XERR-Pad16)") (class "Default")
      (node (ref "U1") (pin "16") (pinfunction "XERR_16") (pintype "bidirectional"))
    )
    (net (code "113") (name "unconnected-(U2-SOUT-Pad17)") (class "Default")
      (node (ref "U2") (pin "17") (pinfunction "SOUT_17") (pintype "bidirectional"))
    )
    (net (code "114") (name "unconnected-(U2-XERR-Pad16)") (class "Default")
      (node (ref "U2") (pin "16") (pinfunction "XERR_16") (pintype "bidirectional"))
    )
    (net (code "115") (name "unconnected-(U3-XERR-Pad16)") (class "Default")
      (node (ref "U3") (pin "16") (pinfunction "XERR_16") (pintype "bidirectional"))
    )
    (net (code "116") (name "unconnected-(U4-XERR-Pad16)") (class "Default")
      (node (ref "U4") (pin "16") (pinfunction "XERR_16") (pintype "bidirectional"))
    )
    (net (code "117") (name "unconnected-(X1B-S-Pad10)") (class "Default")
      (node (ref "X1") (pin "10") (pinfunction "S_10") (pintype "passive"))
    )
    (net (code "118") (name "unconnected-(X1D-S-Pad12)") (class "Default")
      (node (ref "X1") (pin "12") (pinfunction "S_12") (pintype "passive"))
    )
    (net (code "119") (name "unconnected-(X1J-S-Pad18)") (class "Default")
      (node (ref "X1") (pin "18") (pinfunction "S_18") (pintype "passive"))
    )
    (net (code "120") (name "unconnected-(X1K-S-Pad19)") (class "Default")
      (node (ref "X1") (pin "19") (pinfunction "S_19") (pintype "passive"))
    )
    (net (code "121") (name "unconnected-(X1M-S-Pad20)") (class "Default")
      (node (ref "X1") (pin "20") (pinfunction "S_20") (pintype "passive"))
    )
    (net (code "122") (name "unconnected-(X1O-S-Pad4)") (class "Default")
      (node (ref "X1") (pin "4") (pinfunction "S_4") (pintype "passive"))
    )
    (net (code "123") (name "unconnected-(X1Q-S-Pad6)") (class "Default")
      (node (ref "X1") (pin "6") (pinfunction "S_6") (pintype "passive"))
    )
    (net (code "124") (name "unconnected-(X1S-S-Pad8)") (class "Default")
      (node (ref "X1") (pin "8") (pinfunction "S_8") (pintype "passive"))
    )
    (net (code "125") (name "unconnected-(X1T-S-Pad9)") (class "Default")
      (node (ref "X1") (pin "9") (pinfunction "S_9") (pintype "passive"))
    )
  )
)
